# USBC_Protection.net
KiCad netlist of a schematic drawn in Altium Designer
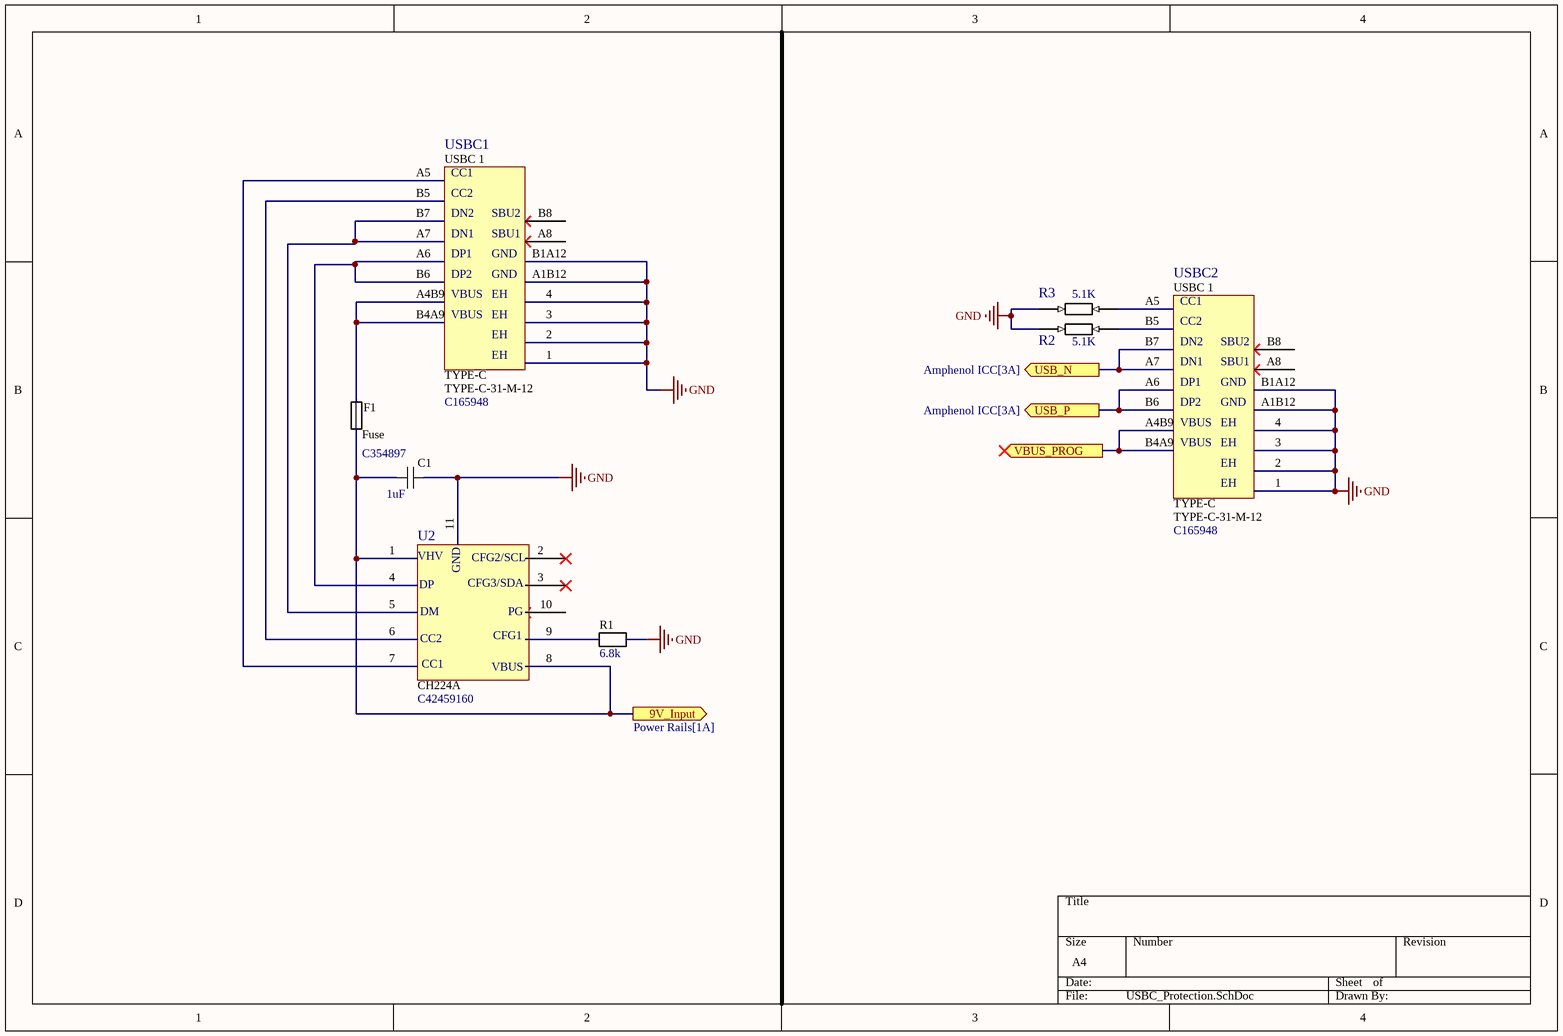
[diagram p0: USBC_Protection.SchDoc]

(export (version "E")
  (design (tool "Eeschema 10.0.6"))
  (components
    (comp (ref "C1")
      (value "1uF")
      (footprint "C0603")
      (description "1uF ±10% 50V Ceramic Capacitor X5R 0603")
      (fields (field (name "Comment") "CL10A105KB8NNNC") (field (name "SOURCE") "LCSC"))
      (libsource (lib "C15849") (part "CL10A105KB8NNNC"))
    )
    (comp (ref "F1")
      (value "Fuse")
      (footprint "F1206")
      (description "3A Fuse Surface Mount 1206")
      (fields (field (name "NAME") "C354897") (field (name "SOURCE") "LCSC"))
      (libsource (lib "C354897") (part "1206T3A63V"))
    )
    (comp (ref "R1")
      (value "6.8k")
      (footprint "R0603")
      (description "6.8kÎ© Â±5% 100mW 0603 Thick Film Resistor AEC-Q200")
      (fields (field (name "Comment") "CQ03WAJ0682T5E") (field (name "SOURCE") "LCSC"))
      (libsource (lib "C2770993") (part "CQ03WAJ0682T5E"))
    )
    (comp (ref "R2")
      (value "5.1K")
      (footprint "R0603")
      (description "5.1kÎ© Â±1% 100mW 0603 Thick Film Resistor")
      (fields (field (name "Comment") "0603WAF5101T5E") (field (name "SOURCE") "LCSC"))
      (libsource (lib "C23186") (part "0603WAF5101T5E"))
    )
    (comp (ref "R3")
      (value "5.1K")
      (footprint "R0603")
      (description "5.1kÎ© Â±1% 100mW 0603 Thick Film Resistor")
      (fields (field (name "Comment") "0603WAF5101T5E") (field (name "SOURCE") "LCSC"))
      (libsource (lib "C23186") (part "0603WAF5101T5E"))
    )
    (comp (ref "U2")
      (value "CH224A")
      (footprint "ESSOP-10_L4.9-W3.9-P1.0-LS6.0-TL-EP")
      (description "Power Receiver Controller 1C 140W ESSOP-10 Power Management - Specialized RoHS")
      (fields (field (name "NAME") "C42459160") (field (name "SOURCE") "LCSC"))
      (libsource (lib "C42459160") (part "CH224A"))
    )
    (comp (ref "USBC1")
      (value "TYPE-C-31-M-12")
      (footprint "USB-C_SMD-TYPE-C-31-M-12_1")
      (description "USB-C (USB TYPE-C) Receptacle Connector 16 Position Surface Mount")
      (fields (field (name "NAME") "C165948") (field (name "SOURCE") "LCSC"))
      (libsource (lib "C165948") (part "TYPE-C-31-M-12"))
    )
    (comp (ref "USBC2")
      (value "TYPE-C-31-M-12")
      (footprint "USB-C_SMD-TYPE-C-31-M-12_1")
      (description "USB-C (USB TYPE-C) Receptacle Connector 16 Position Surface Mount")
      (fields (field (name "NAME") "C165948") (field (name "SOURCE") "LCSC"))
      (libsource (lib "C165948") (part "TYPE-C-31-M-12"))
    )
  )
  (nets
    (net (code "1") (name "/9V_Input") (class "Default")
      (node (ref "C1") (pin "2") (pinfunction "2_2") (pintype "passive"))
      (node (ref "F1") (pin "1") (pinfunction "1_1") (pintype "passive"))
      (node (ref "U2") (pin "1") (pinfunction "1_1") (pintype "passive"))
      (node (ref "U2") (pin "8") (pinfunction "8_8") (pintype "passive"))
    )
    (net (code "2") (name "/USB_N") (class "Default")
      (node (ref "USBC2") (pin "A7") (pinfunction "B14_A7") (pintype "passive"))
      (node (ref "USBC2") (pin "B7") (pinfunction "B13_B7") (pintype "passive"))
    )
    (net (code "3") (name "/USB_P") (class "Default")
      (node (ref "USBC2") (pin "A6") (pinfunction "B15_A6") (pintype "passive"))
      (node (ref "USBC2") (pin "B6") (pinfunction "B16_B6") (pintype "passive"))
    )
    (net (code "4") (name "/VBUS_PROG") (class "Default")
      (node (ref "USBC2") (pin "A4B9") (pinfunction "B9_A4B9") (pintype "passive"))
      (node (ref "USBC2") (pin "B4A9") (pinfunction "B10_B4A9") (pintype "passive"))
    )
    (net (code "5") (name "GND") (class "Default")
      (node (ref "C1") (pin "1") (pinfunction "1_1") (pintype "passive"))
      (node (ref "R1") (pin "2") (pinfunction "2_2") (pintype "passive"))
      (node (ref "R2") (pin "1") (pinfunction "1_1") (pintype "input"))
      (node (ref "R3") (pin "1") (pinfunction "1_1") (pintype "input"))
      (node (ref "U2") (pin "11") (pinfunction "11_11") (pintype "passive"))
      (node (ref "USBC1") (pin "1") (pinfunction "1_1") (pintype "passive"))
      (node (ref "USBC1") (pin "2") (pinfunction "2_2") (pintype "passive"))
      (node (ref "USBC1") (pin "3") (pinfunction "3_3") (pintype "passive"))
      (node (ref "USBC1") (pin "4") (pinfunction "4_4") (pintype "passive"))
      (node (ref "USBC1") (pin "A1B12") (pinfunction "5_A1B12") (pintype "passive"))
      (node (ref "USBC1") (pin "B1A12") (pinfunction "6_B1A12") (pintype "passive"))
      (node (ref "USBC2") (pin "1") (pinfunction "1_1") (pintype "passive"))
      (node (ref "USBC2") (pin "2") (pinfunction "2_2") (pintype "passive"))
      (node (ref "USBC2") (pin "3") (pinfunction "3_3") (pintype "passive"))
      (node (ref "USBC2") (pin "4") (pinfunction "4_4") (pintype "passive"))
      (node (ref "USBC2") (pin "A1B12") (pinfunction "5_A1B12") (pintype "passive"))
      (node (ref "USBC2") (pin "B1A12") (pinfunction "6_B1A12") (pintype "passive"))
    )
    (net (code "6") (name "Net-(R1-Pad1)") (class "Default")
      (node (ref "R1") (pin "1") (pinfunction "1_1") (pintype "passive"))
      (node (ref "U2") (pin "9") (pinfunction "9_9") (pintype "passive"))
    )
    (net (code "7") (name "Net-(USBC1-B10)") (class "Default")
      (node (ref "F1") (pin "2") (pinfunction "2_2") (pintype "passive"))
      (node (ref "USBC1") (pin "A4B9") (pinfunction "B9_A4B9") (pintype "passive"))
      (node (ref "USBC1") (pin "B4A9") (pinfunction "B10_B4A9") (pintype "passive"))
    )
    (net (code "8") (name "Net-(USBC1-B11)") (class "Default")
      (node (ref "U2") (pin "7") (pinfunction "7_7") (pintype "passive"))
      (node (ref "USBC1") (pin "A5") (pinfunction "B11_A5") (pintype "passive"))
    )
    (net (code "9") (name "Net-(USBC1-B12)") (class "Default")
      (node (ref "U2") (pin "6") (pinfunction "6_6") (pintype "passive"))
      (node (ref "USBC1") (pin "B5") (pinfunction "B12_B5") (pintype "passive"))
    )
    (net (code "10") (name "Net-(USBC1-B13)") (class "Default")
      (node (ref "U2") (pin "5") (pinfunction "5_5") (pintype "passive"))
      (node (ref "USBC1") (pin "A7") (pinfunction "B14_A7") (pintype "passive"))
      (node (ref "USBC1") (pin "B7") (pinfunction "B13_B7") (pintype "passive"))
    )
    (net (code "11") (name "Net-(USBC1-B15)") (class "Default")
      (node (ref "U2") (pin "4") (pinfunction "4_4") (pintype "passive"))
      (node (ref "USBC1") (pin "A6") (pinfunction "B15_A6") (pintype "passive"))
      (node (ref "USBC1") (pin "B6") (pinfunction "B16_B6") (pintype "passive"))
    )
    (net (code "12") (name "Net-(USBC2-B11)") (class "Default")
      (node (ref "R3") (pin "2") (pinfunction "2_2") (pintype "input"))
      (node (ref "USBC2") (pin "A5") (pinfunction "B11_A5") (pintype "passive"))
    )
    (net (code "13") (name "Net-(USBC2-B12)") (class "Default")
      (node (ref "R2") (pin "2") (pinfunction "2_2") (pintype "input"))
      (node (ref "USBC2") (pin "B5") (pinfunction "B12_B5") (pintype "passive"))
    )
    (net (code "14") (name "unconnected-(U2-Pad2)") (class "Default")
      (node (ref "U2") (pin "2") (pinfunction "2_2") (pintype "passive+no_connect"))
    )
    (net (code "15") (name "unconnected-(U2-Pad3)") (class "Default")
      (node (ref "U2") (pin "3") (pinfunction "3_3") (pintype "passive+no_connect"))
    )
    (net (code "16") (name "unconnected-(U2-Pad10)") (class "Default")
      (node (ref "U2") (pin "10") (pinfunction "10_10") (pintype "passive+no_connect"))
    )
    (net (code "17") (name "unconnected-(USBC1-7-PadA8)") (class "Default")
      (node (ref "USBC1") (pin "A8") (pinfunction "7_A8") (pintype "passive+no_connect"))
    )
    (net (code "18") (name "unconnected-(USBC1-8-PadB8)") (class "Default")
      (node (ref "USBC1") (pin "B8") (pinfunction "8_B8") (pintype "passive+no_connect"))
    )
    (net (code "19") (name "unconnected-(USBC2-7-PadA8)") (class "Default")
      (node (ref "USBC2") (pin "A8") (pinfunction "7_A8") (pintype "passive+no_connect"))
    )
    (net (code "20") (name "unconnected-(USBC2-8-PadB8)") (class "Default")
      (node (ref "USBC2") (pin "B8") (pinfunction "8_B8") (pintype "passive+no_connect"))
    )
  )
)
